# Interface.net
KiCad netlist of a schematic drawn in Altium Designer
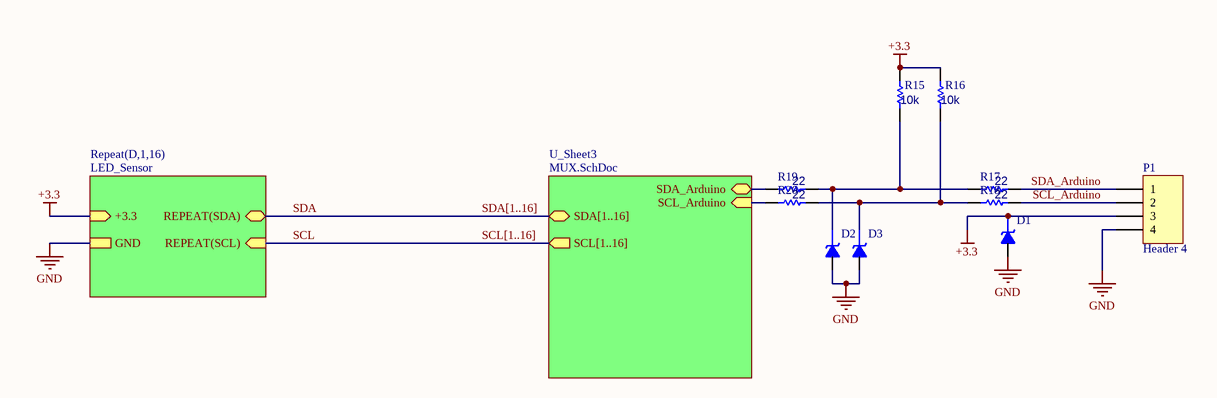
[diagram p0: Interface.SchDoc]

(export (version "E")
  (design (tool "Eeschema 10.0.6"))
  (components
    (comp (ref "D1")
      (value "STS521033B950")
      (footprint "STS521033B950_COB")
      (description "3.3V ESD Diode")
      (fields (field (name "COPYRIGHT") "Copyright (C) 2023 Ultra Librarian. All rights reserved."))
      (libsource (lib "Space Concordia") (part "STS521033B950"))
    )
    (comp (ref "D2")
      (value "STS521033B950")
      (footprint "STS521033B950_COB")
      (description "3.3V ESD Diode")
      (fields (field (name "COPYRIGHT") "Copyright (C) 2023 Ultra Librarian. All rights reserved."))
      (libsource (lib "Space Concordia") (part "STS521033B950"))
    )
    (comp (ref "D3")
      (value "STS521033B950")
      (footprint "STS521033B950_COB")
      (description "3.3V ESD Diode")
      (fields (field (name "COPYRIGHT") "Copyright (C) 2023 Ultra Librarian. All rights reserved."))
      (libsource (lib "Space Concordia") (part "STS521033B950"))
    )
    (comp (ref "P1")
      (value "Header 4")
      (footprint "HDR1X4")
      (description "Header, 4-Pin")
      (fields (field (name "PUBLISHER") "Altium Limited"))
      (libsource (lib "Space Concordia") (part "Header 4H"))
    )
    (comp (ref "R15")
      (value "10k")
      (footprint "R0603A")
      (description "Resistor")
      (libsource (lib "Space Concordia") (part "Resistor"))
    )
    (comp (ref "R16")
      (value "10k")
      (footprint "R0603A")
      (description "Resistor")
      (libsource (lib "Space Concordia") (part "Resistor"))
    )
    (comp (ref "R17")
      (value "22")
      (footprint "R0603A")
      (description "Resistor")
      (libsource (lib "Space Concordia") (part "Resistor"))
    )
    (comp (ref "R18")
      (value "22")
      (footprint "R0603A")
      (description "Resistor")
      (libsource (lib "Space Concordia") (part "Resistor"))
    )
    (comp (ref "R19")
      (value "22")
      (footprint "R0603A")
      (description "Resistor")
      (libsource (lib "Space Concordia") (part "Resistor"))
    )
    (comp (ref "R20")
      (value "22")
      (footprint "R0603A")
      (description "Resistor")
      (libsource (lib "Space Concordia") (part "Resistor"))
    )
  )
  (nets
    (net (code "33") (name "+3.3") (class "Default")
      (node (ref "D1") (pin "1") (pinfunction "K_1") (pintype "passive"))
      (node (ref "P1") (pin "3") (pinfunction "3_3") (pintype "passive"))
      (node (ref "R15") (pin "2") (pinfunction "2_2") (pintype "passive"))
      (node (ref "R16") (pin "2") (pinfunction "2_2") (pintype "passive"))
    )
    (net (code "36") (name "/SCL_Arduino") (class "Default")
      (node (ref "P1") (pin "2") (pinfunction "2_2") (pintype "passive"))
      (node (ref "R18") (pin "1") (pinfunction "1_1") (pintype "passive"))
    )
    (net (code "37") (name "/SCL_Arduino_1") (class "Default")
      (node (ref "R20") (pin "2") (pinfunction "2_2") (pintype "passive"))
    )
    (net (code "40") (name "/SDA_Arduino") (class "Default")
      (node (ref "P1") (pin "1") (pinfunction "1_1") (pintype "passive"))
      (node (ref "R17") (pin "1") (pinfunction "1_1") (pintype "passive"))
    )
    (net (code "41") (name "/SDA_Arduino_1") (class "Default")
      (node (ref "R19") (pin "2") (pinfunction "2_2") (pintype "passive"))
    )
    (net (code "42") (name "GND") (class "Default")
      (node (ref "D1") (pin "2") (pinfunction "A_2") (pintype "passive"))
      (node (ref "D2") (pin "2") (pinfunction "A_2") (pintype "passive"))
      (node (ref "D3") (pin "2") (pinfunction "A_2") (pintype "passive"))
      (node (ref "P1") (pin "4") (pinfunction "4_4") (pintype "passive"))
    )
    (net (code "43") (name "Net-(D2-K)") (class "Default")
      (node (ref "D2") (pin "1") (pinfunction "K_1") (pintype "passive"))
      (node (ref "R15") (pin "1") (pinfunction "1_1") (pintype "passive"))
      (node (ref "R17") (pin "2") (pinfunction "2_2") (pintype "passive"))
      (node (ref "R19") (pin "1") (pinfunction "1_1") (pintype "passive"))
    )
    (net (code "44") (name "Net-(D3-K)") (class "Default")
      (node (ref "D3") (pin "1") (pinfunction "K_1") (pintype "passive"))
      (node (ref "R16") (pin "1") (pinfunction "1_1") (pintype "passive"))
      (node (ref "R18") (pin "2") (pinfunction "2_2") (pintype "passive"))
      (node (ref "R20") (pin "1") (pinfunction "1_1") (pintype "passive"))
    )
  )
)
